# OP_LILYGO_PT2.net
KiCad netlist of a schematic drawn in EAGLE
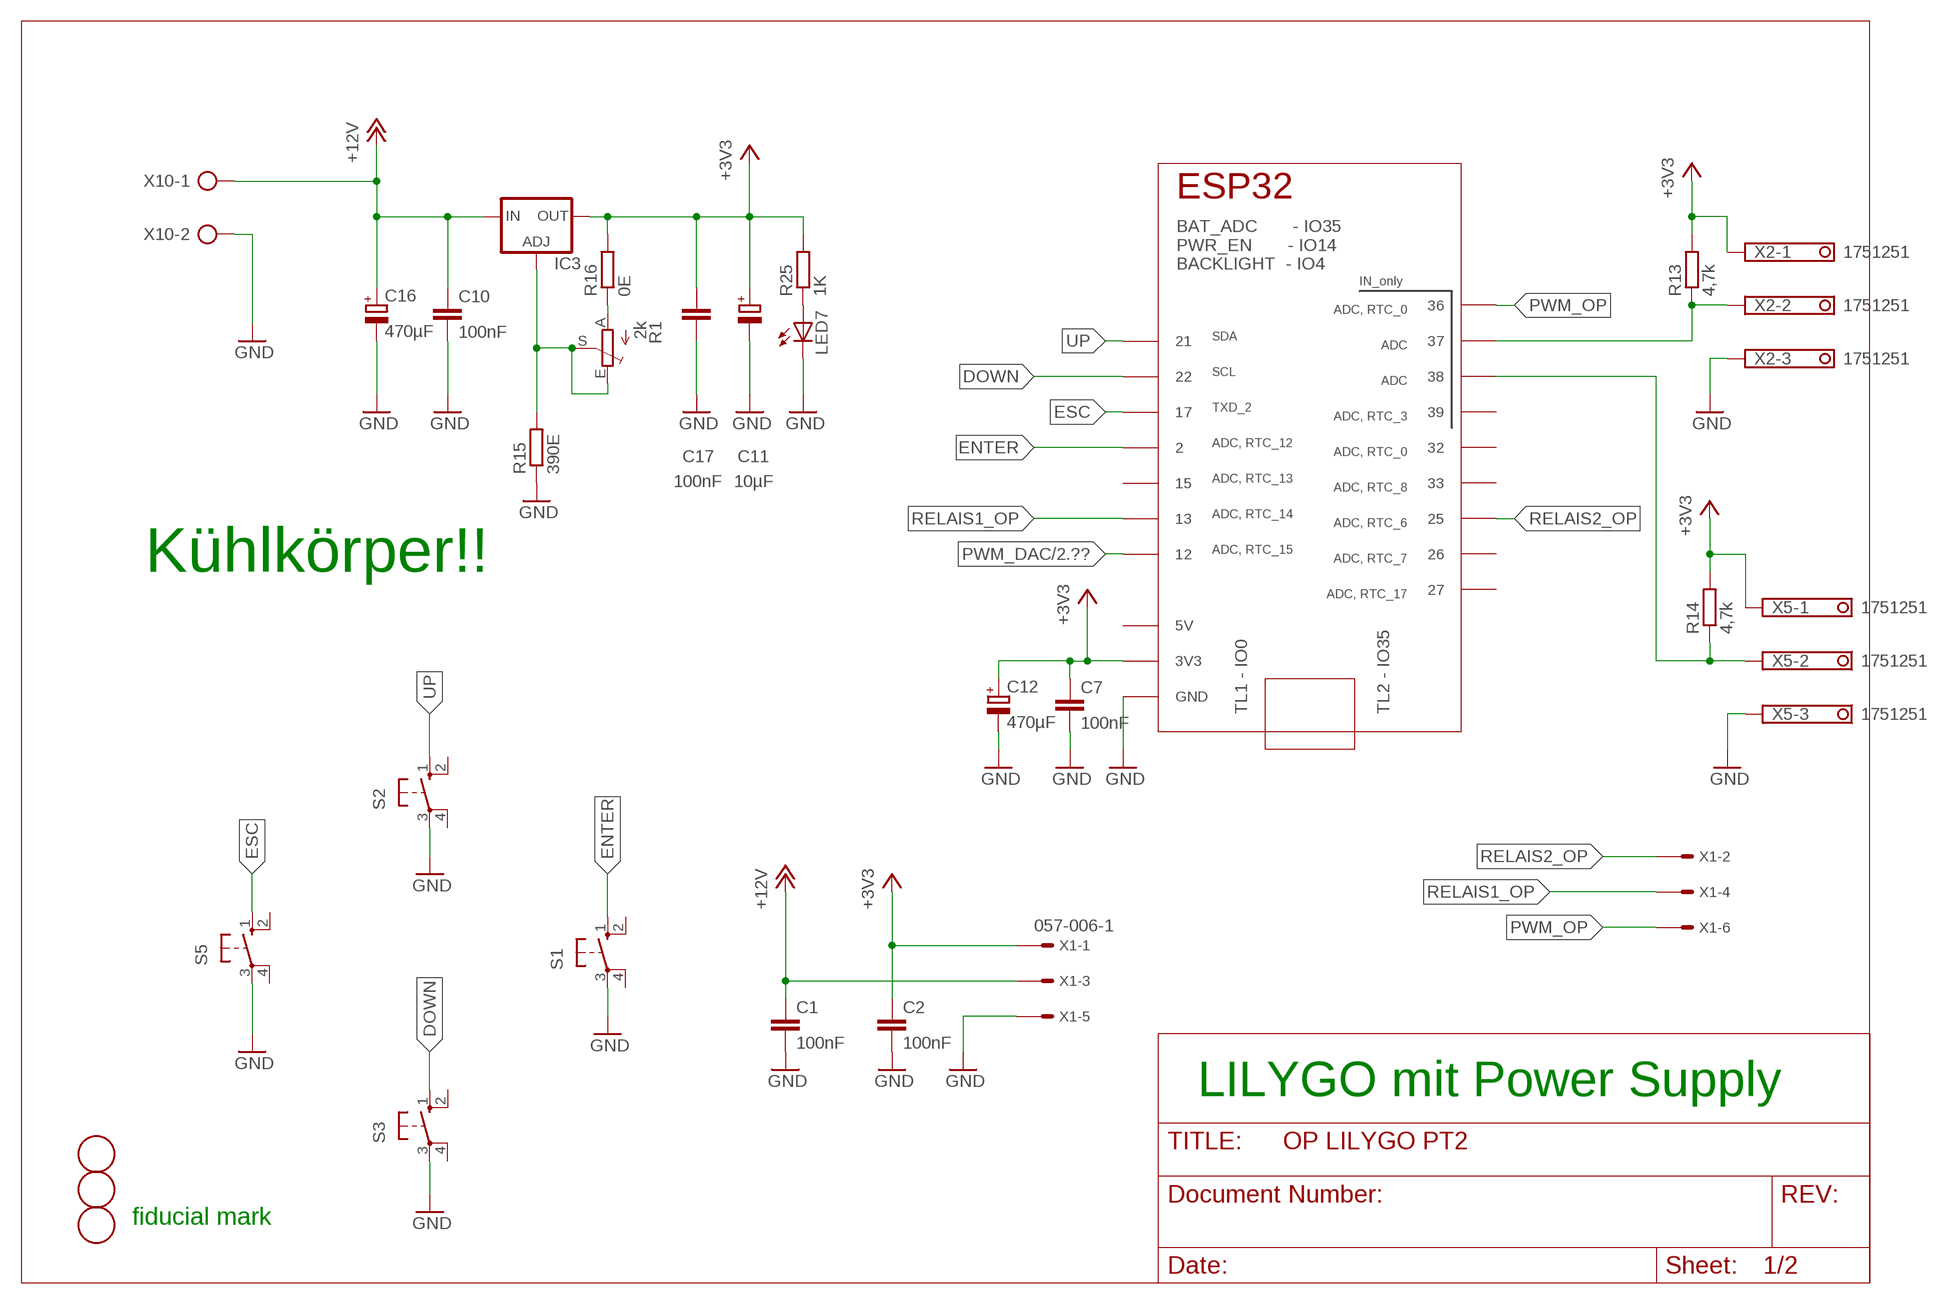
[diagram p0: schematic, sheet 1]
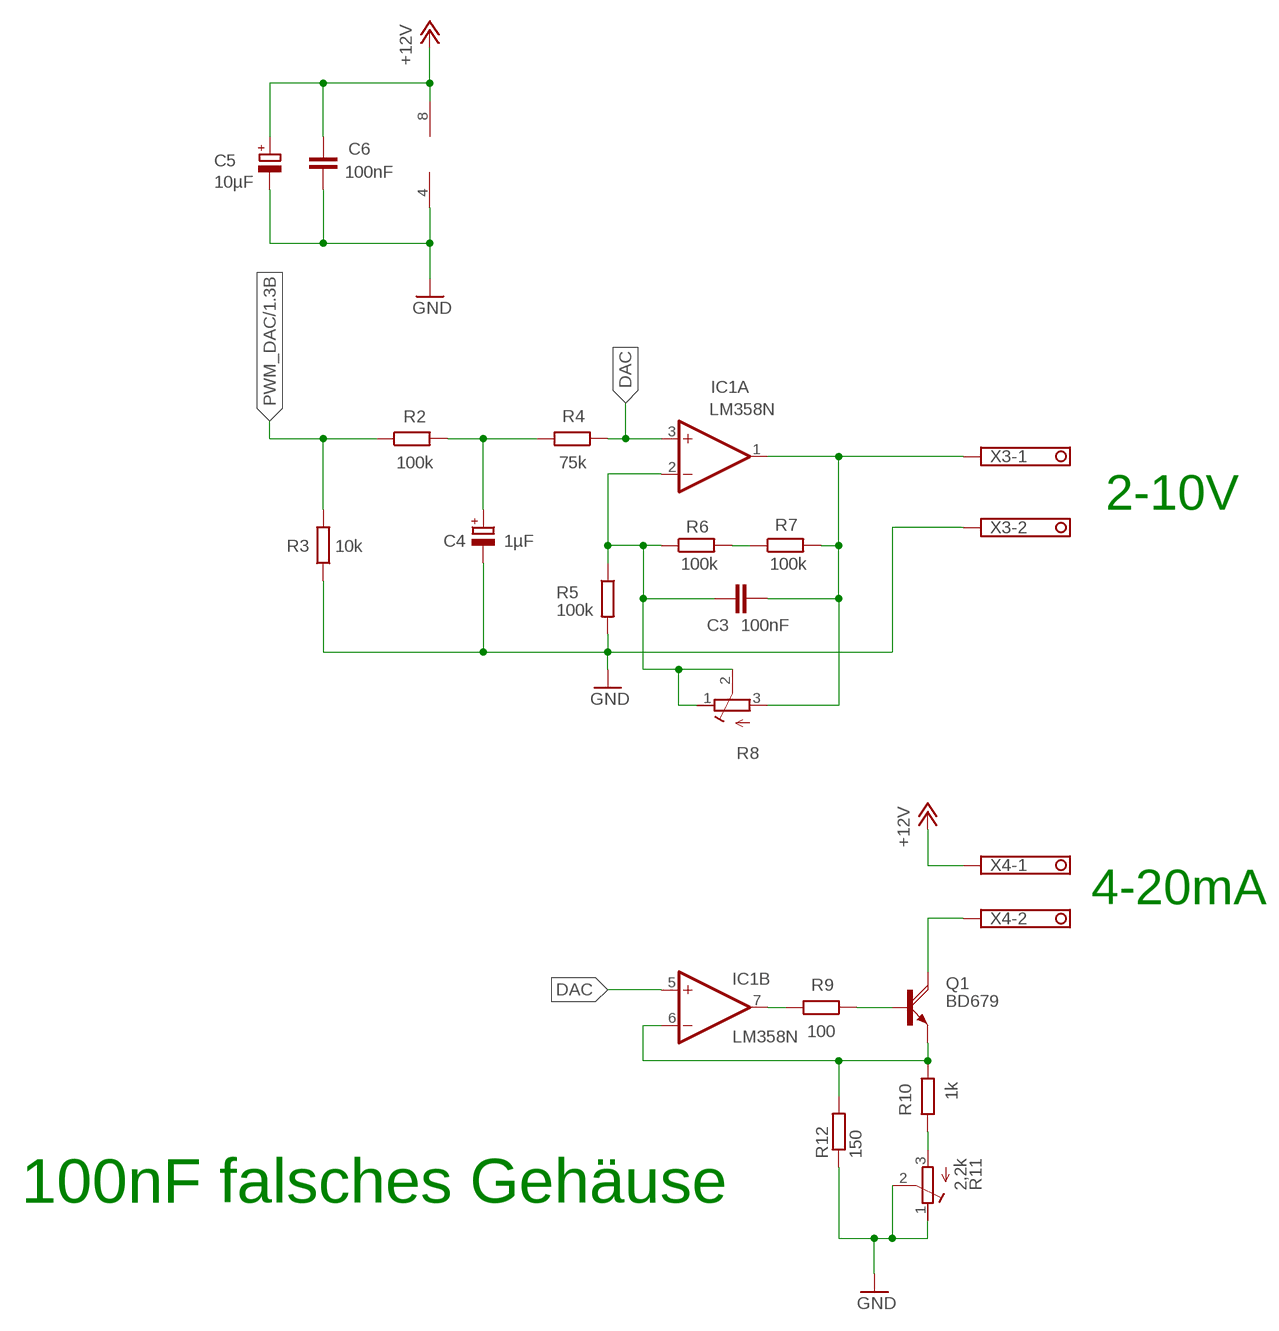
[diagram p1: schematic, sheet 2]

(export (version "E")
  (design (tool "Eeschema 10.0.6"))
  (components
    (comp (ref "C3")
      (value "100nF")
      (footprint "eagle-import:C050-035X075")
      (libsource (lib "eagle-import") (part "C-EU050-035X075"))
    )
    (comp (ref "C4")
      (value "1µF")
      (footprint "eagle-import:E2,5-5")
      (libsource (lib "eagle-import") (part "CPOL-EUE2.5-5"))
    )
    (comp (ref "C5")
      (value "10µF")
      (footprint "eagle-import:E2,5-5")
      (libsource (lib "eagle-import") (part "CPOL-EUE2.5-5"))
    )
    (comp (ref "C6")
      (value "100nF")
      (footprint "eagle-import:C050-035X075")
      (libsource (lib "eagle-import") (part "C-EU050-035X075"))
    )
    (comp (ref "IC1")
      (value "LM358N")
      (footprint "eagle-import:DIL08")
      (libsource (lib "eagle-import") (part "LM358N"))
    )
    (comp (ref "Q1")
      (value "BD679")
      (footprint "eagle-import:TO126AV")
      (libsource (lib "eagle-import") (part "BD679"))
    )
    (comp (ref "R2")
      (value "100k")
      (footprint "eagle-import:0207_2V")
      (libsource (lib "eagle-import") (part "R-EU_0207/2V"))
    )
    (comp (ref "R3")
      (value "10k")
      (footprint "eagle-import:0207_2V")
      (libsource (lib "eagle-import") (part "R-EU_0207/2V"))
    )
    (comp (ref "R4")
      (value "75k")
      (footprint "eagle-import:0207_2V")
      (libsource (lib "eagle-import") (part "R-EU_0207/2V"))
    )
    (comp (ref "R5")
      (value "100k")
      (footprint "eagle-import:0207_2V")
      (libsource (lib "eagle-import") (part "R-EU_0207/2V"))
    )
    (comp (ref "R6")
      (value "100k")
      (footprint "eagle-import:0207_2V")
      (libsource (lib "eagle-import") (part "R-EU_0207/2V"))
    )
    (comp (ref "R7")
      (value "100k")
      (footprint "eagle-import:0207_2V")
      (libsource (lib "eagle-import") (part "R-EU_0207/2V"))
    )
    (comp (ref "R8")
      (value "R-TRIMMT93YA")
      (footprint "eagle-import:RTRIMT93YA")
      (libsource (lib "eagle-import") (part "R-TRIMMT93YA"))
    )
    (comp (ref "R9")
      (value "100")
      (footprint "eagle-import:0207_10")
      (libsource (lib "eagle-import") (part "R-EU_0207/10"))
    )
    (comp (ref "R10")
      (value "1k")
      (footprint "eagle-import:0207_2V")
      (libsource (lib "eagle-import") (part "R-EU_0207/2V"))
    )
    (comp (ref "R11")
      (value "2,2k")
      (footprint "eagle-import:RTRIMT93YA")
      (libsource (lib "eagle-import") (part "R-TRIMMT93YA"))
    )
    (comp (ref "R12")
      (value "150")
      (footprint "eagle-import:0207_12")
      (libsource (lib "eagle-import") (part "R-EU_0207/12"))
    )
    (comp (ref "X3")
      (value "1751248")
      (footprint "eagle-import:1751248")
      (libsource (lib "eagle-import") (part "1751248"))
    )
    (comp (ref "X4")
      (value "1751248")
      (footprint "eagle-import:1751248")
      (libsource (lib "eagle-import") (part "1751248"))
    )
    (comp (ref "C1")
      (value "100nF")
      (footprint "eagle-import:C025-030X050")
      (libsource (lib "eagle-import") (part "C-EU025-030X050"))
    )
    (comp (ref "C2")
      (value "100nF")
      (footprint "eagle-import:C025-030X050")
      (libsource (lib "eagle-import") (part "C-EU025-030X050"))
    )
    (comp (ref "C7")
      (value "100nF")
      (footprint "eagle-import:C025-030X050")
      (libsource (lib "eagle-import") (part "C-EU025-030X050"))
    )
    (comp (ref "C10")
      (value "100nF")
      (footprint "eagle-import:C025-030X050")
      (libsource (lib "eagle-import") (part "C-EU025-030X050"))
    )
    (comp (ref "C11")
      (value "10µF")
      (footprint "eagle-import:E2,5-6")
      (libsource (lib "eagle-import") (part "CPOL-EUE2.5-6"))
    )
    (comp (ref "C12")
      (value "470µF")
      (footprint "eagle-import:E2,5-6")
      (libsource (lib "eagle-import") (part "CPOL-EUE2.5-6"))
    )
    (comp (ref "C16")
      (value "470µF")
      (footprint "eagle-import:E2,5-6")
      (libsource (lib "eagle-import") (part "CPOL-EUE2.5-6"))
    )
    (comp (ref "C17")
      (value "100nF")
      (footprint "eagle-import:C025-030X050")
      (libsource (lib "eagle-import") (part "C-EU025-030X050"))
    )
    (comp (ref "IC3")
      (value "LM317TS")
      (footprint "eagle-import:317TS")
      (libsource (lib "eagle-import") (part "LM317TS"))
    )
    (comp (ref "IC4")
      (value "TTGO_DISP")
      (footprint "eagle-import:TTGO_DISP_DEFAULT")
      (libsource (lib "eagle-import") (part "TTGO_DISP"))
    )
    (comp (ref "LED7")
      (value "LED5MM")
      (footprint "eagle-import:LED5MM")
      (libsource (lib "eagle-import") (part "LED5MM"))
    )
    (comp (ref "R1")
      (value "2k")
      (footprint "eagle-import:S64YW")
      (libsource (lib "eagle-import") (part "TRIM_1234-S64YW"))
    )
    (comp (ref "R13")
      (value "4,7k")
      (footprint "eagle-import:0207_12")
      (libsource (lib "eagle-import") (part "R-EU_0207/12"))
    )
    (comp (ref "R14")
      (value "4,7k")
      (footprint "eagle-import:0207_12")
      (libsource (lib "eagle-import") (part "R-EU_0207/12"))
    )
    (comp (ref "R15")
      (value "390E")
      (footprint "eagle-import:0207_12")
      (libsource (lib "eagle-import") (part "R-EU_0207/12"))
    )
    (comp (ref "R16")
      (value "0E")
      (footprint "eagle-import:0207_12")
      (libsource (lib "eagle-import") (part "R-EU_0207/12"))
    )
    (comp (ref "R25")
      (value "1K")
      (footprint "eagle-import:0207_12")
      (libsource (lib "eagle-import") (part "R-EU_0207/12"))
    )
    (comp (ref "S1")
      (value "10-XX")
      (footprint "eagle-import:B3F-10XX")
      (fields (field (name "MPN") "B3F-1000"))
      (libsource (lib "eagle-import") (part "10-XX"))
    )
    (comp (ref "S2")
      (value "10-XX")
      (footprint "eagle-import:B3F-10XX")
      (fields (field (name "MPN") "B3F-1000"))
      (libsource (lib "eagle-import") (part "10-XX"))
    )
    (comp (ref "S3")
      (value "10-XX")
      (footprint "eagle-import:B3F-10XX")
      (fields (field (name "MPN") "B3F-1000"))
      (libsource (lib "eagle-import") (part "10-XX"))
    )
    (comp (ref "S5")
      (value "10-XX")
      (footprint "eagle-import:B3F-10XX")
      (fields (field (name "MPN") "B3F-1000"))
      (libsource (lib "eagle-import") (part "10-XX"))
    )
    (comp (ref "U$2")
      (value "FIDUCIALMOUNT")
      (footprint "eagle-import:FIDUCIA-MOUNT")
      (libsource (lib "eagle-import") (part "FIDUCIALMOUNT"))
    )
    (comp (ref "U$7")
      (value "FIDUCIALMOUNT")
      (footprint "eagle-import:FIDUCIA-MOUNT")
      (libsource (lib "eagle-import") (part "FIDUCIALMOUNT"))
    )
    (comp (ref "U$8")
      (value "FIDUCIALMOUNT")
      (footprint "eagle-import:FIDUCIA-MOUNT")
      (libsource (lib "eagle-import") (part "FIDUCIALMOUNT"))
    )
    (comp (ref "X1")
      (value "057-006-1")
      (footprint "eagle-import:057-006-1")
      (libsource (lib "eagle-import") (part "057-006-1"))
    )
    (comp (ref "X2")
      (value "1751251")
      (footprint "eagle-import:1751251")
      (libsource (lib "eagle-import") (part "1751251"))
    )
    (comp (ref "X5")
      (value "1751251")
      (footprint "eagle-import:1751251")
      (libsource (lib "eagle-import") (part "1751251"))
    )
    (comp (ref "X10")
      (value "SMKDSP_1,5/2")
      (footprint "eagle-import:SMKDSP_1,5_2")
      (fields (field (name "MF") "FARNELL") (field (name "MPN") "1733570"))
      (libsource (lib "eagle-import") (part "SMKDSP_1,5/2"))
    )
  )
  (nets
    (net (code "1") (name "+3V3") (class "Default")
      (node (ref "C11") (pin "+") (pinfunction "+_+") (pintype "passive"))
      (node (ref "C12") (pin "+") (pinfunction "+_+") (pintype "passive"))
      (node (ref "C17") (pin "1") (pinfunction "1_1") (pintype "passive"))
      (node (ref "C2") (pin "1") (pinfunction "1_1") (pintype "passive"))
      (node (ref "C7") (pin "1") (pinfunction "1_1") (pintype "passive"))
      (node (ref "IC3") (pin "2") (pinfunction "OUT_2") (pintype "passive"))
      (node (ref "IC4") (pin "3V3_1") (pinfunction "3V3_3V3_1") (pintype "bidirectional"))
      (node (ref "IC4") (pin "3V3_2") (pinfunction "3V3_3V3_2") (pintype "bidirectional"))
      (node (ref "R13") (pin "2") (pinfunction "2_2") (pintype "passive"))
      (node (ref "R14") (pin "2") (pinfunction "2_2") (pintype "passive"))
      (node (ref "R16") (pin "2") (pinfunction "2_2") (pintype "passive"))
      (node (ref "R25") (pin "2") (pinfunction "2_2") (pintype "passive"))
      (node (ref "X1") (pin "1") (pinfunction "S_1") (pintype "passive"))
      (node (ref "X2") (pin "1") (pinfunction "K_1") (pintype "passive"))
      (node (ref "X5") (pin "1") (pinfunction "K_1") (pintype "passive"))
    )
    (net (code "2") (name "+12V") (class "Default")
      (node (ref "C1") (pin "1") (pinfunction "1_1") (pintype "passive"))
      (node (ref "C10") (pin "1") (pinfunction "1_1") (pintype "passive"))
      (node (ref "C16") (pin "+") (pinfunction "+_+") (pintype "passive"))
      (node (ref "C5") (pin "+") (pinfunction "+_+") (pintype "passive"))
      (node (ref "C6") (pin "1") (pinfunction "1_1") (pintype "passive"))
      (node (ref "IC1") (pin "8") (pinfunction "V+_8") (pintype "power_in"))
      (node (ref "IC3") (pin "3") (pinfunction "IN_3") (pintype "input"))
      (node (ref "X1") (pin "3") (pinfunction "S_3") (pintype "passive"))
      (node (ref "X10") (pin "1") (pinfunction "KL_1") (pintype "passive"))
      (node (ref "X4") (pin "1") (pinfunction "K_1") (pintype "passive"))
    )
    (net (code "3") (name "DAC") (class "Default")
      (node (ref "IC1") (pin "3") (pinfunction "+IN_3") (pintype "input"))
      (node (ref "IC1") (pin "5") (pinfunction "+IN_5") (pintype "input"))
      (node (ref "R4") (pin "1") (pinfunction "1_1") (pintype "passive"))
    )
    (net (code "4") (name "DOWN") (class "Default")
      (node (ref "IC4") (pin "22") (pinfunction "22_22") (pintype "bidirectional"))
      (node (ref "S3") (pin "1") (pinfunction "S_1") (pintype "passive"))
    )
    (net (code "5") (name "ENTER") (class "Default")
      (node (ref "IC4") (pin "2") (pinfunction "2_2") (pintype "bidirectional"))
      (node (ref "S1") (pin "1") (pinfunction "S_1") (pintype "passive"))
    )
    (net (code "6") (name "ESC") (class "Default")
      (node (ref "IC4") (pin "17") (pinfunction "17_17") (pintype "bidirectional"))
      (node (ref "S5") (pin "1") (pinfunction "S_1") (pintype "passive"))
    )
    (net (code "7") (name "GND") (class "Default")
      (node (ref "C1") (pin "2") (pinfunction "2_2") (pintype "passive"))
      (node (ref "C10") (pin "2") (pinfunction "2_2") (pintype "passive"))
      (node (ref "C11") (pin "-") (pinfunction "-_-") (pintype "passive"))
      (node (ref "C12") (pin "-") (pinfunction "-_-") (pintype "passive"))
      (node (ref "C16") (pin "-") (pinfunction "-_-") (pintype "passive"))
      (node (ref "C17") (pin "2") (pinfunction "2_2") (pintype "passive"))
      (node (ref "C2") (pin "2") (pinfunction "2_2") (pintype "passive"))
      (node (ref "C4") (pin "-") (pinfunction "-_-") (pintype "passive"))
      (node (ref "C5") (pin "-") (pinfunction "-_-") (pintype "passive"))
      (node (ref "C6") (pin "2") (pinfunction "2_2") (pintype "passive"))
      (node (ref "C7") (pin "2") (pinfunction "2_2") (pintype "passive"))
      (node (ref "IC1") (pin "4") (pinfunction "V-_4") (pintype "power_in"))
      (node (ref "IC4") (pin "GND_1") (pinfunction "GND_GND_1") (pintype "bidirectional"))
      (node (ref "IC4") (pin "GND_2") (pinfunction "GND_GND_2") (pintype "bidirectional"))
      (node (ref "IC4") (pin "GND_3") (pinfunction "GND_GND_3") (pintype "bidirectional"))
      (node (ref "IC4") (pin "GND_4") (pinfunction "GND_GND_4") (pintype "bidirectional"))
      (node (ref "IC4") (pin "GND_5") (pinfunction "GND_GND_5") (pintype "bidirectional"))
      (node (ref "LED7") (pin "K") (pinfunction "C_K") (pintype "passive"))
      (node (ref "R11") (pin "1") (pinfunction "E_1") (pintype "passive"))
      (node (ref "R11") (pin "2") (pinfunction "S_2") (pintype "passive"))
      (node (ref "R12") (pin "1") (pinfunction "1_1") (pintype "passive"))
      (node (ref "R15") (pin "1") (pinfunction "1_1") (pintype "passive"))
      (node (ref "R3") (pin "1") (pinfunction "1_1") (pintype "passive"))
      (node (ref "R5") (pin "2") (pinfunction "2_2") (pintype "passive"))
      (node (ref "S1") (pin "3") (pinfunction "P_3") (pintype "passive"))
      (node (ref "S2") (pin "3") (pinfunction "P_3") (pintype "passive"))
      (node (ref "S3") (pin "3") (pinfunction "P_3") (pintype "passive"))
      (node (ref "S5") (pin "3") (pinfunction "P_3") (pintype "passive"))
      (node (ref "X1") (pin "5") (pinfunction "S_5") (pintype "passive"))
      (node (ref "X10") (pin "2") (pinfunction "KL_2") (pintype "passive"))
      (node (ref "X2") (pin "3") (pinfunction "K_3") (pintype "passive"))
      (node (ref "X3") (pin "2") (pinfunction "K_2") (pintype "passive"))
      (node (ref "X5") (pin "3") (pinfunction "K_3") (pintype "passive"))
    )
    (net (code "8") (name "Net-(C4-Pad+)") (class "Default")
      (node (ref "C4") (pin "+") (pinfunction "+_+") (pintype "passive"))
      (node (ref "R2") (pin "2") (pinfunction "2_2") (pintype "passive"))
      (node (ref "R4") (pin "2") (pinfunction "2_2") (pintype "passive"))
    )
    (net (code "9") (name "Net-(IC1A--IN)") (class "Default")
      (node (ref "C3") (pin "1") (pinfunction "1_1") (pintype "passive"))
      (node (ref "IC1") (pin "2") (pinfunction "-IN_2") (pintype "input"))
      (node (ref "R5") (pin "1") (pinfunction "1_1") (pintype "passive"))
      (node (ref "R6") (pin "1") (pinfunction "1_1") (pintype "passive"))
      (node (ref "R8") (pin "1") (pinfunction "E_1") (pintype "passive"))
      (node (ref "R8") (pin "2") (pinfunction "S_2") (pintype "passive"))
    )
    (net (code "10") (name "Net-(IC1A-OUT)") (class "Default")
      (node (ref "C3") (pin "2") (pinfunction "2_2") (pintype "passive"))
      (node (ref "IC1") (pin "1") (pinfunction "OUT_1") (pintype "output"))
      (node (ref "R7") (pin "2") (pinfunction "2_2") (pintype "passive"))
      (node (ref "R8") (pin "3") (pinfunction "A_3") (pintype "passive"))
      (node (ref "X3") (pin "1") (pinfunction "K_1") (pintype "passive"))
    )
    (net (code "11") (name "Net-(IC1B--IN)") (class "Default")
      (node (ref "IC1") (pin "6") (pinfunction "-IN_6") (pintype "input"))
      (node (ref "Q1") (pin "E") (pinfunction "E_E") (pintype "passive"))
      (node (ref "R10") (pin "1") (pinfunction "1_1") (pintype "passive"))
      (node (ref "R12") (pin "2") (pinfunction "2_2") (pintype "passive"))
    )
    (net (code "12") (name "Net-(IC1B-OUT)") (class "Default")
      (node (ref "IC1") (pin "7") (pinfunction "OUT_7") (pintype "output"))
      (node (ref "R9") (pin "2") (pinfunction "2_2") (pintype "passive"))
    )
    (net (code "13") (name "Net-(IC3-ADJ)") (class "Default")
      (node (ref "IC3") (pin "1") (pinfunction "ADJ_1") (pintype "input"))
      (node (ref "R1") (pin "E") (pinfunction "E_E") (pintype "passive"))
      (node (ref "R1") (pin "S") (pinfunction "S_S") (pintype "passive"))
      (node (ref "R15") (pin "2") (pinfunction "2_2") (pintype "passive"))
    )
    (net (code "14") (name "Net-(LED7-PadA)") (class "Default")
      (node (ref "LED7") (pin "A") (pinfunction "A_A") (pintype "passive"))
      (node (ref "R25") (pin "1") (pinfunction "1_1") (pintype "passive"))
    )
    (net (code "15") (name "Net-(Q1-PadB)") (class "Default")
      (node (ref "Q1") (pin "B") (pinfunction "B_B") (pintype "passive"))
      (node (ref "R9") (pin "1") (pinfunction "1_1") (pintype "passive"))
    )
    (net (code "16") (name "Net-(R1-PadA)") (class "Default")
      (node (ref "R1") (pin "A") (pinfunction "A_A") (pintype "passive"))
      (node (ref "R16") (pin "1") (pinfunction "1_1") (pintype "passive"))
    )
    (net (code "17") (name "Net-(R6-Pad2)") (class "Default")
      (node (ref "R6") (pin "2") (pinfunction "2_2") (pintype "passive"))
      (node (ref "R7") (pin "1") (pinfunction "1_1") (pintype "passive"))
    )
    (net (code "18") (name "Net-(R11-A)") (class "Default")
      (node (ref "R10") (pin "2") (pinfunction "2_2") (pintype "passive"))
      (node (ref "R11") (pin "3") (pinfunction "A_3") (pintype "passive"))
    )
    (net (code "19") (name "Net-(X2B-K)") (class "Default")
      (node (ref "IC4") (pin "37") (pinfunction "37_37") (pintype "bidirectional"))
      (node (ref "R13") (pin "1") (pinfunction "1_1") (pintype "passive"))
      (node (ref "X2") (pin "2") (pinfunction "K_2") (pintype "passive"))
    )
    (net (code "20") (name "Net-(X4B-K)") (class "Default")
      (node (ref "Q1") (pin "C") (pinfunction "C_C") (pintype "passive"))
      (node (ref "X4") (pin "2") (pinfunction "K_2") (pintype "passive"))
    )
    (net (code "21") (name "Net-(X5B-K)") (class "Default")
      (node (ref "IC4") (pin "38") (pinfunction "38_38") (pintype "bidirectional"))
      (node (ref "R14") (pin "1") (pinfunction "1_1") (pintype "passive"))
      (node (ref "X5") (pin "2") (pinfunction "K_2") (pintype "passive"))
    )
    (net (code "22") (name "PWM_DAC") (class "Default")
      (node (ref "IC4") (pin "12") (pinfunction "12_12") (pintype "bidirectional"))
      (node (ref "R2") (pin "1") (pinfunction "1_1") (pintype "passive"))
      (node (ref "R3") (pin "2") (pinfunction "2_2") (pintype "passive"))
    )
    (net (code "23") (name "PWM_OP") (class "Default")
      (node (ref "IC4") (pin "36") (pinfunction "36_36") (pintype "bidirectional"))
      (node (ref "X1") (pin "6") (pinfunction "S_6") (pintype "passive"))
    )
    (net (code "24") (name "RELAIS1_OP") (class "Default")
      (node (ref "IC4") (pin "13") (pinfunction "13_13") (pintype "bidirectional"))
      (node (ref "X1") (pin "4") (pinfunction "S_4") (pintype "passive"))
    )
    (net (code "25") (name "RELAIS2_OP") (class "Default")
      (node (ref "IC4") (pin "25") (pinfunction "25_25") (pintype "bidirectional"))
      (node (ref "X1") (pin "2") (pinfunction "S_2") (pintype "passive"))
    )
    (net (code "26") (name "UP") (class "Default")
      (node (ref "IC4") (pin "21") (pinfunction "21_21") (pintype "bidirectional"))
      (node (ref "S2") (pin "1") (pinfunction "S_1") (pintype "passive"))
    )
    (net (code "27") (name "unconnected-(IC4-Pad5V)") (class "Default")
      (node (ref "IC4") (pin "5V") (pinfunction "5V_5V") (pintype "bidirectional"))
    )
    (net (code "28") (name "unconnected-(IC4-Pad15)") (class "Default")
      (node (ref "IC4") (pin "15") (pinfunction "15_15") (pintype "bidirectional"))
    )
    (net (code "29") (name "unconnected-(IC4-Pad26)") (class "Default")
      (node (ref "IC4") (pin "26") (pinfunction "26_26") (pintype "bidirectional"))
    )
    (net (code "30") (name "unconnected-(IC4-Pad27)") (class "Default")
      (node (ref "IC4") (pin "27") (pinfunction "27_27") (pintype "bidirectional"))
    )
    (net (code "31") (name "unconnected-(IC4-Pad32)") (class "Default")
      (node (ref "IC4") (pin "32") (pinfunction "32_32") (pintype "bidirectional"))
    )
    (net (code "32") (name "unconnected-(IC4-Pad33)") (class "Default")
      (node (ref "IC4") (pin "33") (pinfunction "33_33") (pintype "bidirectional"))
    )
    (net (code "33") (name "unconnected-(IC4-Pad39)") (class "Default")
      (node (ref "IC4") (pin "39") (pinfunction "39_39") (pintype "bidirectional"))
    )
    (net (code "34") (name "unconnected-(R1-S-PadS@1)") (class "Default")
      (node (ref "R1") (pin "S@1") (pinfunction "S_S@1") (pintype "passive"))
    )
    (net (code "35") (name "unconnected-(S1-P1-Pad4)") (class "Default")
      (node (ref "S1") (pin "4") (pinfunction "P1_4") (pintype "passive"))
    )
    (net (code "36") (name "unconnected-(S1-S1-Pad2)") (class "Default")
      (node (ref "S1") (pin "2") (pinfunction "S1_2") (pintype "passive"))
    )
    (net (code "37") (name "unconnected-(S2-P1-Pad4)") (class "Default")
      (node (ref "S2") (pin "4") (pinfunction "P1_4") (pintype "passive"))
    )
    (net (code "38") (name "unconnected-(S2-S1-Pad2)") (class "Default")
      (node (ref "S2") (pin "2") (pinfunction "S1_2") (pintype "passive"))
    )
    (net (code "39") (name "unconnected-(S3-P1-Pad4)") (class "Default")
      (node (ref "S3") (pin "4") (pinfunction "P1_4") (pintype "passive"))
    )
    (net (code "40") (name "unconnected-(S3-S1-Pad2)") (class "Default")
      (node (ref "S3") (pin "2") (pinfunction "S1_2") (pintype "passive"))
    )
    (net (code "41") (name "unconnected-(S5-P1-Pad4)") (class "Default")
      (node (ref "S5") (pin "4") (pinfunction "P1_4") (pintype "passive"))
    )
    (net (code "42") (name "unconnected-(S5-S1-Pad2)") (class "Default")
      (node (ref "S5") (pin "2") (pinfunction "S1_2") (pintype "passive"))
    )
  )
)
